# AVR_Tag-Connect.net
KiCad netlist of a schematic drawn in EAGLE
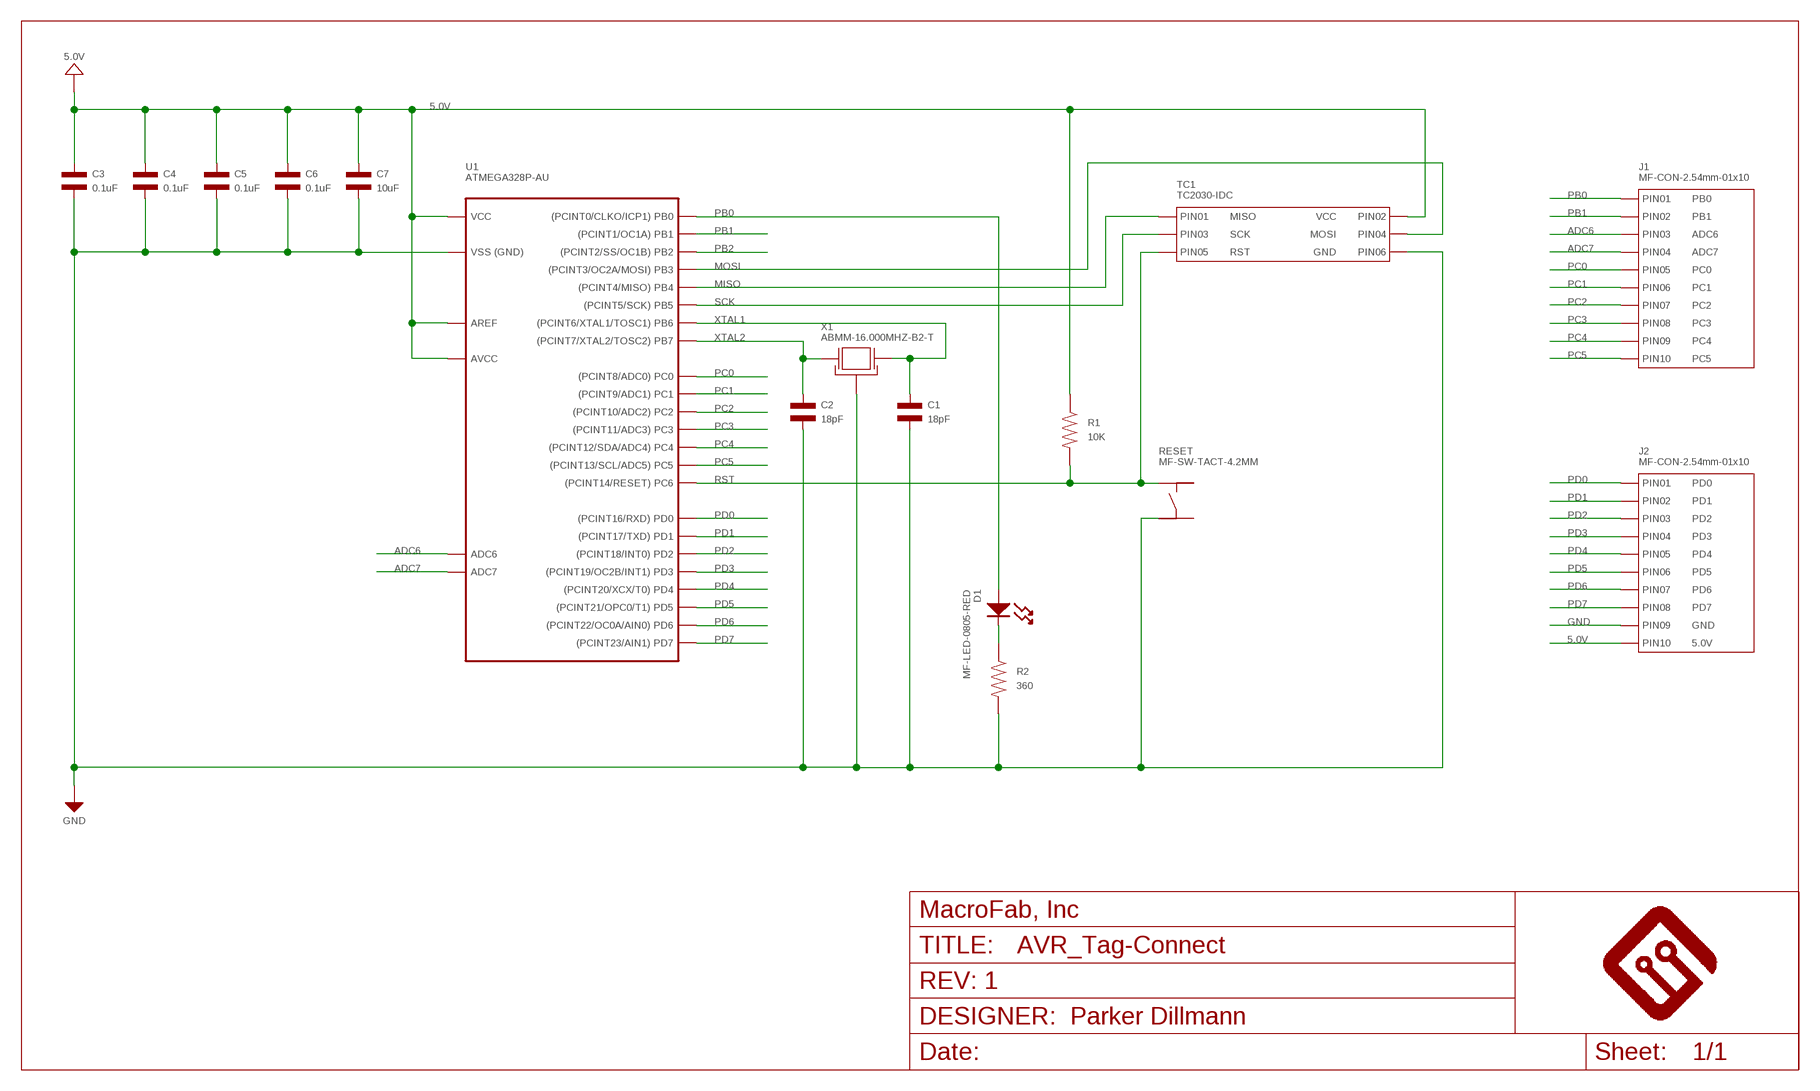
[diagram p0: schematic, sheet 1]

(export (version "E")
  (design (tool "Eeschema 10.0.6"))
  (components
    (comp (ref "C1")
      (value "18pF")
      (footprint "eagle-import:C0805")
      (fields (field (name "MPN") "08055A180JAT2A"))
      (libsource (lib "eagle-import") (part "CAPACITOR_NP_0805"))
    )
    (comp (ref "C2")
      (value "18pF")
      (footprint "eagle-import:C0805")
      (fields (field (name "MPN") "08055A180JAT2A"))
      (libsource (lib "eagle-import") (part "CAPACITOR_NP_0805"))
    )
    (comp (ref "C3")
      (value "0.1uF")
      (footprint "eagle-import:C0805")
      (fields (field (name "MPN") "MF-CAP-0805-0.1uF"))
      (libsource (lib "eagle-import") (part "CAPACITOR_NP_0805"))
    )
    (comp (ref "C4")
      (value "0.1uF")
      (footprint "eagle-import:C0805")
      (fields (field (name "MPN") "MF-CAP-0805-0.1uF"))
      (libsource (lib "eagle-import") (part "CAPACITOR_NP_0805"))
    )
    (comp (ref "C5")
      (value "0.1uF")
      (footprint "eagle-import:C0805")
      (fields (field (name "MPN") "MF-CAP-0805-0.1uF"))
      (libsource (lib "eagle-import") (part "CAPACITOR_NP_0805"))
    )
    (comp (ref "C6")
      (value "0.1uF")
      (footprint "eagle-import:C0805")
      (fields (field (name "MPN") "MF-CAP-0805-0.1uF"))
      (libsource (lib "eagle-import") (part "CAPACITOR_NP_0805"))
    )
    (comp (ref "C7")
      (value "10uF")
      (footprint "eagle-import:C1206")
      (fields (field (name "MPN") "MF-CAP-1206-10uF"))
      (libsource (lib "eagle-import") (part "CAPACITOR_NP_1206"))
    )
    (comp (ref "D1")
      (value "MF-LED-0805-RED")
      (footprint "eagle-import:LED0805")
      (fields (field (name "HOUSEPART") "YES"))
      (libsource (lib "eagle-import") (part "LED_SINGLE-0805-RED"))
    )
    (comp (ref "FRAME1")
      (value "MF_FRAMEDEFAULT")
      (footprint "eagle-import:MF_FRAME_DEFAULT")
      (fields
        (field (name "HOUSEPART") "0")
        (field (name "DNAME") "Parker Dillmann")
        (field (name "REVNUM") "REV: 1")
      )
      (libsource (lib "eagle-import") (part "MF_FRAMEDEFAULT"))
    )
    (comp (ref "J1")
      (value "MF-CON-2.54mm-01x10")
      (footprint "eagle-import:PTH_2.54MM_01X10")
      (fields
        (field (name "HOUSEPART") "YES")
        (field (name "LABEL01") "PB0")
        (field (name "LABEL02") "PB1")
        (field (name "LABEL03") "ADC6")
        (field (name "LABEL04") "ADC7")
        (field (name "LABEL05") "PC0")
        (field (name "LABEL06") "PC1")
        (field (name "LABEL07") "PC2")
        (field (name "LABEL08") "PC3")
        (field (name "LABEL09") "PC4")
        (field (name "LABEL10") "PC5")
      )
      (libsource (lib "eagle-import") (part "CON_01X10_PTH_2.54MM"))
    )
    (comp (ref "J2")
      (value "MF-CON-2.54mm-01x10")
      (footprint "eagle-import:PTH_2.54MM_01X10")
      (fields
        (field (name "HOUSEPART") "YES")
        (field (name "LABEL01") "PD0")
        (field (name "LABEL02") "PD1")
        (field (name "LABEL03") "PD2")
        (field (name "LABEL04") "PD3")
        (field (name "LABEL05") "PD4")
        (field (name "LABEL06") "PD5")
        (field (name "LABEL07") "PD6")
        (field (name "LABEL08") "PD7")
        (field (name "LABEL09") "GND")
        (field (name "LABEL10") "5.0V")
      )
      (libsource (lib "eagle-import") (part "CON_01X10_PTH_2.54MM"))
    )
    (comp (ref "R1")
      (value "10K")
      (footprint "eagle-import:R0805")
      (fields (field (name "MPN") "MF-RES-0805-10K"))
      (libsource (lib "eagle-import") (part "RESISTOR_0805"))
    )
    (comp (ref "R2")
      (value "360")
      (footprint "eagle-import:R0805")
      (fields (field (name "MPN") "MF-RES-0805-360"))
      (libsource (lib "eagle-import") (part "RESISTOR_0805"))
    )
    (comp (ref "RESET")
      (value "MF-SW-TACT-4.2MM")
      (footprint "eagle-import:TACT4.2MM")
      (fields (field (name "HOUSEPART") "YES"))
      (libsource (lib "eagle-import") (part "TACT_4.2MM"))
    )
    (comp (ref "TC1")
      (value "TC2030-IDC")
      (footprint "eagle-import:TC2030-IDC-FP")
      (fields (field (name "HOUSEPART") "NO"))
      (libsource (lib "eagle-import") (part "CON_02X03_TC2030-IDC_AVRISP"))
    )
    (comp (ref "U1")
      (value "ATMEGA328P-AU")
      (footprint "eagle-import:TQFP32")
      (fields (field (name "HOUSEPART") "NO"))
      (libsource (lib "eagle-import") (part "ATMEGA328P-AU"))
    )
    (comp (ref "X1")
      (value "ABMM-16.000MHZ-B2-T")
      (footprint "eagle-import:7MMX5MM")
      (fields (field (name "HOUSEPART") "NO") (field (name "MPN") "ABMM-16.000MHZ-B2-T"))
      (libsource (lib "eagle-import") (part "CYRSTAL_GND_ABMM"))
    )
  )
  (nets
    (net (code "1") (name "/ADC6") (class "Default")
      (node (ref "J1") (pin "P$3") (pinfunction "PIN3_P$3") (pintype "bidirectional"))
      (node (ref "U1") (pin "P$19") (pinfunction "ADC6_P$19") (pintype "bidirectional"))
    )
    (net (code "2") (name "/ADC7") (class "Default")
      (node (ref "J1") (pin "P$4") (pinfunction "PIN4_P$4") (pintype "bidirectional"))
      (node (ref "U1") (pin "P$22") (pinfunction "ADC7_P$22") (pintype "bidirectional"))
    )
    (net (code "3") (name "/MISO") (class "Default")
      (node (ref "TC1") (pin "P$1") (pinfunction "PIN1_P$1") (pintype "bidirectional"))
      (node (ref "U1") (pin "P$16") (pinfunction "PB4_P$16") (pintype "bidirectional"))
    )
    (net (code "4") (name "/MOSI") (class "Default")
      (node (ref "TC1") (pin "P$4") (pinfunction "PIN4_P$4") (pintype "bidirectional"))
      (node (ref "U1") (pin "P$15") (pinfunction "PB3_P$15") (pintype "bidirectional"))
    )
    (net (code "5") (name "/PB0") (class "Default")
      (node (ref "D1") (pin "ANODE") (pinfunction "ANODE_ANODE") (pintype "power_in"))
      (node (ref "J1") (pin "P$1") (pinfunction "PIN1_P$1") (pintype "bidirectional"))
      (node (ref "U1") (pin "P$12") (pinfunction "PB0_P$12") (pintype "bidirectional"))
    )
    (net (code "6") (name "/PB1") (class "Default")
      (node (ref "J1") (pin "P$2") (pinfunction "PIN2_P$2") (pintype "bidirectional"))
      (node (ref "U1") (pin "P$13") (pinfunction "PB1_P$13") (pintype "bidirectional"))
    )
    (net (code "7") (name "/PB2") (class "Default")
      (node (ref "U1") (pin "P$14") (pinfunction "PB2_P$14") (pintype "bidirectional"))
    )
    (net (code "8") (name "/PC0") (class "Default")
      (node (ref "J1") (pin "P$5") (pinfunction "PIN5_P$5") (pintype "bidirectional"))
      (node (ref "U1") (pin "P$23") (pinfunction "PC0_P$23") (pintype "bidirectional"))
    )
    (net (code "9") (name "/PC1") (class "Default")
      (node (ref "J1") (pin "P$6") (pinfunction "PIN6_P$6") (pintype "bidirectional"))
      (node (ref "U1") (pin "P$24") (pinfunction "PC1_P$24") (pintype "bidirectional"))
    )
    (net (code "10") (name "/PC2") (class "Default")
      (node (ref "J1") (pin "P$7") (pinfunction "PIN7_P$7") (pintype "bidirectional"))
      (node (ref "U1") (pin "P$25") (pinfunction "PC2_P$25") (pintype "bidirectional"))
    )
    (net (code "11") (name "/PC3") (class "Default")
      (node (ref "J1") (pin "P$8") (pinfunction "PIN8_P$8") (pintype "bidirectional"))
      (node (ref "U1") (pin "P$26") (pinfunction "PC3_P$26") (pintype "bidirectional"))
    )
    (net (code "12") (name "/PC4") (class "Default")
      (node (ref "J1") (pin "P$9") (pinfunction "PIN9_P$9") (pintype "bidirectional"))
      (node (ref "U1") (pin "P$27") (pinfunction "PC4_P$27") (pintype "bidirectional"))
    )
    (net (code "13") (name "/PC5") (class "Default")
      (node (ref "J1") (pin "P$10") (pinfunction "PIN10_P$10") (pintype "bidirectional"))
      (node (ref "U1") (pin "P$28") (pinfunction "PC5_P$28") (pintype "bidirectional"))
    )
    (net (code "14") (name "/PD0") (class "Default")
      (node (ref "J2") (pin "P$1") (pinfunction "PIN1_P$1") (pintype "bidirectional"))
      (node (ref "U1") (pin "P$30") (pinfunction "PD0_P$30") (pintype "bidirectional"))
    )
    (net (code "15") (name "/PD1") (class "Default")
      (node (ref "J2") (pin "P$2") (pinfunction "PIN2_P$2") (pintype "bidirectional"))
      (node (ref "U1") (pin "P$31") (pinfunction "PD1_P$31") (pintype "bidirectional"))
    )
    (net (code "16") (name "/PD2") (class "Default")
      (node (ref "J2") (pin "P$3") (pinfunction "PIN3_P$3") (pintype "bidirectional"))
      (node (ref "U1") (pin "P$32") (pinfunction "PD2_P$32") (pintype "bidirectional"))
    )
    (net (code "17") (name "/PD3") (class "Default")
      (node (ref "J2") (pin "P$4") (pinfunction "PIN4_P$4") (pintype "bidirectional"))
      (node (ref "U1") (pin "P$1") (pinfunction "PD3_P$1") (pintype "bidirectional"))
    )
    (net (code "18") (name "/PD4") (class "Default")
      (node (ref "J2") (pin "P$5") (pinfunction "PIN5_P$5") (pintype "bidirectional"))
      (node (ref "U1") (pin "P$2") (pinfunction "PD4_P$2") (pintype "bidirectional"))
    )
    (net (code "19") (name "/PD5") (class "Default")
      (node (ref "J2") (pin "P$6") (pinfunction "PIN6_P$6") (pintype "bidirectional"))
      (node (ref "U1") (pin "P$9") (pinfunction "PD5_P$9") (pintype "bidirectional"))
    )
    (net (code "20") (name "/PD6") (class "Default")
      (node (ref "J2") (pin "P$7") (pinfunction "PIN7_P$7") (pintype "bidirectional"))
      (node (ref "U1") (pin "P$10") (pinfunction "PD6_P$10") (pintype "bidirectional"))
    )
    (net (code "21") (name "/PD7") (class "Default")
      (node (ref "J2") (pin "P$8") (pinfunction "PIN8_P$8") (pintype "bidirectional"))
      (node (ref "U1") (pin "P$11") (pinfunction "PD7_P$11") (pintype "bidirectional"))
    )
    (net (code "22") (name "/RST") (class "Default")
      (node (ref "R1") (pin "P$2") (pinfunction "P$2_P$2") (pintype "passive"))
      (node (ref "RESET") (pin "P$1") (pinfunction "P$1_P$1") (pintype "bidirectional"))
      (node (ref "TC1") (pin "P$5") (pinfunction "PIN5_P$5") (pintype "bidirectional"))
      (node (ref "U1") (pin "P$29") (pinfunction "PC6_P$29") (pintype "bidirectional"))
    )
    (net (code "23") (name "/SCK") (class "Default")
      (node (ref "TC1") (pin "P$3") (pinfunction "PIN3_P$3") (pintype "bidirectional"))
      (node (ref "U1") (pin "P$17") (pinfunction "PB5_P$17") (pintype "bidirectional"))
    )
    (net (code "24") (name "/XTAL1") (class "Default")
      (node (ref "C1") (pin "P$1") (pinfunction "P$1_P$1") (pintype "passive"))
      (node (ref "U1") (pin "P$7") (pinfunction "PB6_P$7") (pintype "bidirectional"))
      (node (ref "X1") (pin "P$3") (pinfunction "X1_P$3") (pintype "bidirectional"))
    )
    (net (code "25") (name "/XTAL2") (class "Default")
      (node (ref "C2") (pin "P$1") (pinfunction "P$1_P$1") (pintype "passive"))
      (node (ref "U1") (pin "P$8") (pinfunction "PB7_P$8") (pintype "bidirectional"))
      (node (ref "X1") (pin "P$1") (pinfunction "X0_P$1") (pintype "bidirectional"))
    )
    (net (code "26") (name "5.0V") (class "Default")
      (node (ref "C3") (pin "P$1") (pinfunction "P$1_P$1") (pintype "passive"))
      (node (ref "C4") (pin "P$1") (pinfunction "P$1_P$1") (pintype "passive"))
      (node (ref "C5") (pin "P$1") (pinfunction "P$1_P$1") (pintype "passive"))
      (node (ref "C6") (pin "P$1") (pinfunction "P$1_P$1") (pintype "passive"))
      (node (ref "C7") (pin "P$1") (pinfunction "P$1_P$1") (pintype "passive"))
      (node (ref "J2") (pin "P$10") (pinfunction "PIN10_P$10") (pintype "bidirectional"))
      (node (ref "R1") (pin "P$1") (pinfunction "P$1_P$1") (pintype "passive"))
      (node (ref "TC1") (pin "P$2") (pinfunction "PIN2_P$2") (pintype "bidirectional"))
      (node (ref "U1") (pin "P$18") (pinfunction "AVCC_P$18") (pintype "power_in"))
      (node (ref "U1") (pin "P$20") (pinfunction "AREF_P$20") (pintype "power_in"))
      (node (ref "U1") (pin "P$4") (pinfunction "VCC_P$4") (pintype "power_in"))
      (node (ref "U1") (pin "P$6") (pinfunction "VCC_P$6") (pintype "power_in"))
    )
    (net (code "27") (name "GND") (class "Default")
      (node (ref "C1") (pin "P$2") (pinfunction "P$2_P$2") (pintype "passive"))
      (node (ref "C2") (pin "P$2") (pinfunction "P$2_P$2") (pintype "passive"))
      (node (ref "C3") (pin "P$2") (pinfunction "P$2_P$2") (pintype "passive"))
      (node (ref "C4") (pin "P$2") (pinfunction "P$2_P$2") (pintype "passive"))
      (node (ref "C5") (pin "P$2") (pinfunction "P$2_P$2") (pintype "passive"))
      (node (ref "C6") (pin "P$2") (pinfunction "P$2_P$2") (pintype "passive"))
      (node (ref "C7") (pin "P$2") (pinfunction "P$2_P$2") (pintype "passive"))
      (node (ref "J2") (pin "P$9") (pinfunction "PIN9_P$9") (pintype "bidirectional"))
      (node (ref "R2") (pin "P$2") (pinfunction "P$2_P$2") (pintype "passive"))
      (node (ref "RESET") (pin "P$3") (pinfunction "P$3_P$3") (pintype "bidirectional"))
      (node (ref "TC1") (pin "P$6") (pinfunction "PIN6_P$6") (pintype "bidirectional"))
      (node (ref "U1") (pin "P$21") (pinfunction "GND_P$21") (pintype "power_in"))
      (node (ref "U1") (pin "P$3") (pinfunction "GND_P$3") (pintype "power_in"))
      (node (ref "U1") (pin "P$5") (pinfunction "GND_P$5") (pintype "power_in"))
      (node (ref "X1") (pin "P$2") (pinfunction "GND_P$2") (pintype "bidirectional"))
      (node (ref "X1") (pin "P$4") (pinfunction "GND_P$4") (pintype "bidirectional"))
    )
    (net (code "28") (name "Net-(D1-PadCATHODE)") (class "Default")
      (node (ref "D1") (pin "CATHODE") (pinfunction "CATHODE_CATHODE") (pintype "power_in"))
      (node (ref "R2") (pin "P$1") (pinfunction "P$1_P$1") (pintype "passive"))
    )
    (net (code "29") (name "unconnected-(RESET-PadP$2)") (class "Default")
      (node (ref "RESET") (pin "P$2") (pinfunction "P$2_P$2") (pintype "bidirectional"))
    )
    (net (code "30") (name "unconnected-(RESET-PadP$4)") (class "Default")
      (node (ref "RESET") (pin "P$4") (pinfunction "P$4_P$4") (pintype "bidirectional"))
    )
  )
)
